# BaseStationCPU.net
KiCad netlist of a schematic drawn in Altium Designer
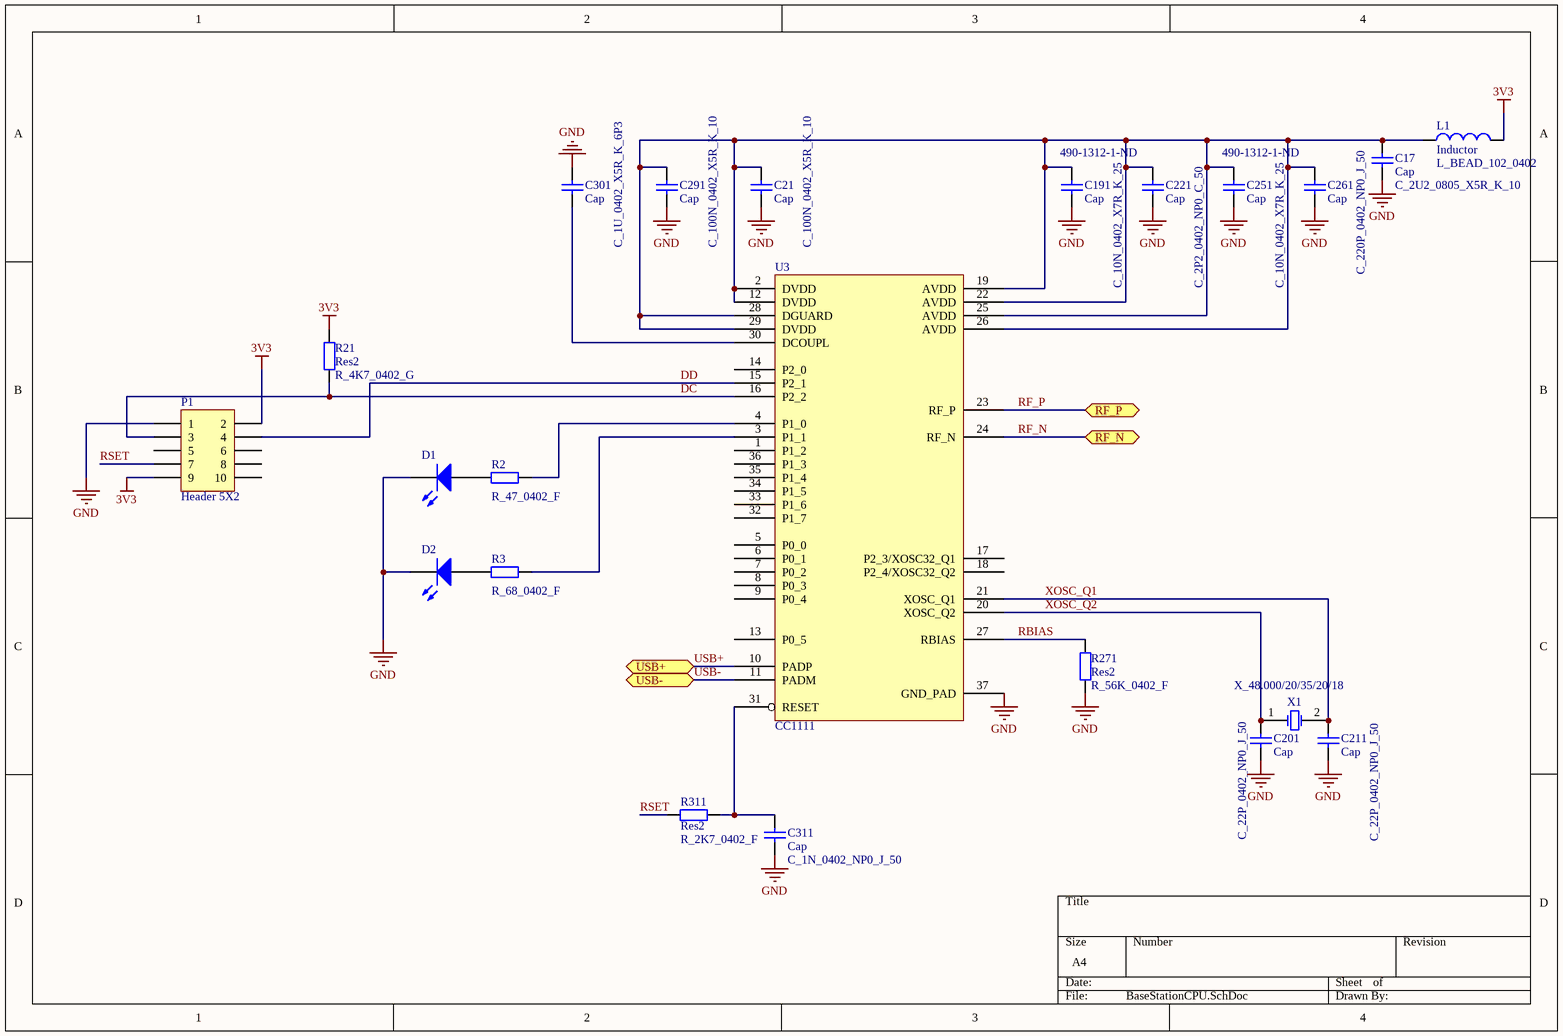
[diagram p0: BaseStationCPU.SchDoc]

(export (version "E")
  (design (tool "Eeschema 10.0.6"))
  (components
    (comp (ref "C17")
      (value "Cap")
      (footprint "C_0805")
      (description "Capacitor")
      (fields (field (name "ALTIUM_VALUE") "C_2U2_0805_X5R_K_10") (field (name "PUBLISHER") "Altium Limited"))
      (libsource (lib "Miscellaneous Devices") (part "Cap"))
    )
    (comp (ref "C21")
      (value "Cap")
      (footprint "C_0402")
      (description "Capacitor")
      (fields
        (field (name "ALTIUM_VALUE") "C_100N_0402_X5R_K_10")
        (field (name "PUBLISHER") "Altium Limited")
      )
      (libsource (lib "Miscellaneous Devices") (part "Cap"))
    )
    (comp (ref "C191")
      (value "Cap")
      (footprint "C_0402")
      (description "Capacitor")
      (fields
        (field (name "ALTIUM_VALUE") "C_10N_0402_X7R_K_25")
        (field (name "SUPPLIER PART NUMBER 1") "490-1312-1-ND")
        (field (name "PUBLISHER") "Altium Limited")
      )
      (libsource (lib "Miscellaneous Devices") (part "Cap"))
    )
    (comp (ref "C201")
      (value "Cap")
      (footprint "C_0402")
      (description "Capacitor")
      (fields (field (name "ALTIUM_VALUE") "C_22P_0402_NP0_J_50") (field (name "PUBLISHER") "Altium Limited"))
      (libsource (lib "Miscellaneous Devices") (part "Cap"))
    )
    (comp (ref "C211")
      (value "Cap")
      (footprint "C_0402")
      (description "Capacitor")
      (fields (field (name "ALTIUM_VALUE") "C_22P_0402_NP0_J_50") (field (name "PUBLISHER") "Altium Limited"))
      (libsource (lib "Miscellaneous Devices") (part "Cap"))
    )
    (comp (ref "C221")
      (value "Cap")
      (footprint "C_0402")
      (description "Capacitor")
      (fields (field (name "ALTIUM_VALUE") "C_2P2_0402_NP0_C_50") (field (name "PUBLISHER") "Altium Limited"))
      (libsource (lib "Miscellaneous Devices") (part "Cap"))
    )
    (comp (ref "C251")
      (value "Cap")
      (footprint "C_0402")
      (description "Capacitor")
      (fields
        (field (name "ALTIUM_VALUE") "C_10N_0402_X7R_K_25")
        (field (name "SUPPLIER PART NUMBER 1") "490-1312-1-ND")
        (field (name "PUBLISHER") "Altium Limited")
      )
      (libsource (lib "Miscellaneous Devices") (part "Cap"))
    )
    (comp (ref "C261")
      (value "Cap")
      (footprint "C_0402")
      (description "Capacitor")
      (fields
        (field (name "ALTIUM_VALUE") "C_220P_0402_NP0_J_50")
        (field (name "PUBLISHER") "Altium Limited")
      )
      (libsource (lib "Miscellaneous Devices") (part "Cap"))
    )
    (comp (ref "C291")
      (value "Cap")
      (footprint "C_0402")
      (description "Capacitor")
      (fields
        (field (name "ALTIUM_VALUE") "C_100N_0402_X5R_K_10")
        (field (name "PUBLISHER") "Altium Limited")
      )
      (libsource (lib "Miscellaneous Devices") (part "Cap"))
    )
    (comp (ref "C301")
      (value "Cap")
      (footprint "C_0402")
      (description "Capacitor")
      (fields (field (name "ALTIUM_VALUE") "C_1U_0402_X5R_K_6P3") (field (name "PUBLISHER") "Altium Limited"))
      (libsource (lib "Miscellaneous Devices") (part "Cap"))
    )
    (comp (ref "C311")
      (value "Cap")
      (footprint "C_0402")
      (description "Capacitor")
      (fields (field (name "ALTIUM_VALUE") "C_1N_0402_NP0_J_50") (field (name "PUBLISHER") "Altium Limited"))
      (libsource (lib "Miscellaneous Devices") (part "Cap"))
    )
    (comp (ref "D1")
      (value "LED_EL19-21SYGC")
      (footprint "R_0603")
      (description "LED ALINGAP YW/GN CLEAR 0603 SMD")
      (fields (field (name "PUBLISHER") "Altium Limited"))
      (libsource (lib "Miscellaneous Devices") (part "LED2"))
    )
    (comp (ref "D2")
      (value "LED_EL19-21SYGC")
      (footprint "R_0603")
      (description "LED 660NM RED WTR CLR 0603 SMD")
      (fields (field (name "PUBLISHER") "Altium Limited"))
      (libsource (lib "Miscellaneous Devices") (part "LED2"))
    )
    (comp (ref "L1")
      (value "Inductor")
      (footprint "R_0402")
      (fields (field (name "ALTIUM_VALUE") "L_BEAD_102_0402") (field (name "PUBLISHER") "Altium Limited"))
      (libsource (lib "Miscellaneous Devices") (part "Inductor"))
    )
    (comp (ref "P1")
      (value "Header 5X2")
      (footprint "SMD HEADER")
      (description "Header, 5-Pin, Dual row")
      (fields (field (name "PUBLISHER") "Altium Limited"))
      (libsource (lib "Miscellaneous Connectors") (part "Header 5X2"))
    )
    (comp (ref "R2")
      (value "R_47_0402_F")
      (footprint "R_0402")
      (description "Resistor")
      (fields (field (name "Comment") "Res2") (field (name "PUBLISHER") "Altium Limited"))
      (libsource (lib "Miscellaneous Devices") (part "Res2"))
    )
    (comp (ref "R3")
      (value "R_68_0402_F")
      (footprint "R_0402")
      (description "Resistor")
      (fields (field (name "Comment") "Res2") (field (name "PUBLISHER") "Altium Limited"))
      (libsource (lib "Miscellaneous Devices") (part "Res2"))
    )
    (comp (ref "R21")
      (value "Res2")
      (footprint "R_0402")
      (description "Resistor")
      (fields (field (name "ALTIUM_VALUE") "R_4K7_0402_G") (field (name "PUBLISHER") "Altium Limited"))
      (libsource (lib "") (part "Res2_1"))
    )
    (comp (ref "R271")
      (value "Res2")
      (footprint "R_0402")
      (description "Resistor")
      (fields (field (name "ALTIUM_VALUE") "R_56K_0402_F") (field (name "PUBLISHER") "Altium Limited"))
      (libsource (lib "") (part "Res2_1"))
    )
    (comp (ref "R311")
      (value "Res2")
      (footprint "R_0402")
      (description "Resistor")
      (fields (field (name "ALTIUM_VALUE") "R_2K7_0402_F") (field (name "PUBLISHER") "Altium Limited"))
      (libsource (lib "Miscellaneous Devices") (part "Res2"))
    )
    (comp (ref "U3")
      (value "CC1111")
      (footprint "TI_QFP36")
      (description "RF Microcontrollers (MCU) True System-on-Chip")
      (fields
        (field (name "MANUFACTURER") "Texas Instruments")
        (field (name "MANUFACTURER PART NUMBER") "CC1110F32RSPR")
      )
      (libsource (lib "BrewBit") (part "CC1111"))
    )
    (comp (ref "X1")
      (value "X_48.000/20/35/20/18")
      (footprint "CX3225GB48000D0HEQZ1")
      (description "Crystal Oscillator")
      (fields (field (name "PUBLISHER") "Altium Limited"))
      (libsource (lib "Miscellaneous Devices") (part "XTAL"))
    )
  )
  (nets
    (net (code "1") (name "/DC") (class "Default")
      (node (ref "P1") (pin "3") (pinfunction "3_3") (pintype "passive"))
      (node (ref "R21") (pin "1") (pinfunction "1_1") (pintype "passive"))
      (node (ref "U3") (pin "16") (pinfunction "P2_2_16") (pintype "passive"))
    )
    (net (code "2") (name "/DD") (class "Default")
      (node (ref "P1") (pin "4") (pinfunction "4_4") (pintype "passive"))
      (node (ref "U3") (pin "15") (pinfunction "P2_1_15") (pintype "passive"))
    )
    (net (code "3") (name "/RBIAS") (class "Default")
      (node (ref "R271") (pin "2") (pinfunction "2_2") (pintype "passive"))
      (node (ref "U3") (pin "27") (pinfunction "RBIAS_27") (pintype "passive"))
    )
    (net (code "4") (name "/RF_N") (class "Default")
      (node (ref "U3") (pin "24") (pinfunction "RF_N_24") (pintype "passive"))
    )
    (net (code "5") (name "/RF_P") (class "Default")
      (node (ref "U3") (pin "23") (pinfunction "RF_P_23") (pintype "passive"))
    )
    (net (code "6") (name "/RSET") (class "Default")
      (node (ref "P1") (pin "7") (pinfunction "7_7") (pintype "passive"))
      (node (ref "R311") (pin "1") (pinfunction "1_1") (pintype "passive"))
    )
    (net (code "7") (name "/USB+") (class "Default")
      (node (ref "U3") (pin "10") (pinfunction "PADP_10") (pintype "passive"))
    )
    (net (code "8") (name "/USB-") (class "Default")
      (node (ref "U3") (pin "11") (pinfunction "PADM_11") (pintype "passive"))
    )
    (net (code "9") (name "/XOSC_Q1") (class "Default")
      (node (ref "C211") (pin "2") (pinfunction "2_2") (pintype "passive"))
      (node (ref "U3") (pin "21") (pinfunction "XOSC_Q1_21") (pintype "passive"))
      (node (ref "X1") (pin "2") (pinfunction "OSC2_2") (pintype "passive"))
    )
    (net (code "10") (name "/XOSC_Q2") (class "Default")
      (node (ref "C201") (pin "2") (pinfunction "2_2") (pintype "passive"))
      (node (ref "U3") (pin "20") (pinfunction "XOSC_Q2_20") (pintype "passive"))
      (node (ref "X1") (pin "1") (pinfunction "OSC1_1") (pintype "passive"))
    )
    (net (code "11") (name "3V3") (class "Default")
      (node (ref "L1") (pin "2") (pinfunction "2_2") (pintype "passive"))
      (node (ref "P1") (pin "2") (pinfunction "2_2") (pintype "passive"))
      (node (ref "P1") (pin "9") (pinfunction "9_9") (pintype "passive"))
      (node (ref "R21") (pin "2") (pinfunction "2_2") (pintype "passive"))
    )
    (net (code "12") (name "GND") (class "Default")
      (node (ref "C17") (pin "1") (pinfunction "1_1") (pintype "passive"))
      (node (ref "C191") (pin "1") (pinfunction "1_1") (pintype "passive"))
      (node (ref "C201") (pin "1") (pinfunction "1_1") (pintype "passive"))
      (node (ref "C21") (pin "1") (pinfunction "1_1") (pintype "passive"))
      (node (ref "C211") (pin "1") (pinfunction "1_1") (pintype "passive"))
      (node (ref "C221") (pin "1") (pinfunction "1_1") (pintype "passive"))
      (node (ref "C251") (pin "1") (pinfunction "1_1") (pintype "passive"))
      (node (ref "C261") (pin "1") (pinfunction "1_1") (pintype "passive"))
      (node (ref "C291") (pin "1") (pinfunction "1_1") (pintype "passive"))
      (node (ref "C301") (pin "2") (pinfunction "2_2") (pintype "passive"))
      (node (ref "C311") (pin "1") (pinfunction "1_1") (pintype "passive"))
      (node (ref "D1") (pin "2") (pinfunction "K_2") (pintype "passive"))
      (node (ref "D2") (pin "2") (pinfunction "K_2") (pintype "passive"))
      (node (ref "P1") (pin "1") (pinfunction "1_1") (pintype "passive"))
      (node (ref "R271") (pin "1") (pinfunction "1_1") (pintype "passive"))
      (node (ref "U3") (pin "37") (pinfunction "GND_PAD_37") (pintype "passive"))
    )
    (net (code "13") (name "Net-(D1-A)") (class "Default")
      (node (ref "D1") (pin "1") (pinfunction "A_1") (pintype "passive"))
      (node (ref "R2") (pin "1") (pinfunction "1_1") (pintype "passive"))
    )
    (net (code "14") (name "Net-(D2-A)") (class "Default")
      (node (ref "D2") (pin "1") (pinfunction "A_1") (pintype "passive"))
      (node (ref "R3") (pin "1") (pinfunction "1_1") (pintype "passive"))
    )
    (net (code "15") (name "Net-(U3-DCOUPL)") (class "Default")
      (node (ref "C301") (pin "1") (pinfunction "1_1") (pintype "passive"))
      (node (ref "U3") (pin "30") (pinfunction "DCOUPL_30") (pintype "passive"))
    )
    (net (code "16") (name "Net-(U3-DGUARD)") (class "Default")
      (node (ref "C17") (pin "2") (pinfunction "2_2") (pintype "passive"))
      (node (ref "C191") (pin "2") (pinfunction "2_2") (pintype "passive"))
      (node (ref "C21") (pin "2") (pinfunction "2_2") (pintype "passive"))
      (node (ref "C221") (pin "2") (pinfunction "2_2") (pintype "passive"))
      (node (ref "C251") (pin "2") (pinfunction "2_2") (pintype "passive"))
      (node (ref "C261") (pin "2") (pinfunction "2_2") (pintype "passive"))
      (node (ref "C291") (pin "2") (pinfunction "2_2") (pintype "passive"))
      (node (ref "L1") (pin "1") (pinfunction "1_1") (pintype "passive"))
      (node (ref "U3") (pin "12") (pinfunction "DVDD_12") (pintype "passive"))
      (node (ref "U3") (pin "19") (pinfunction "AVDD_19") (pintype "passive"))
      (node (ref "U3") (pin "2") (pinfunction "DVDD_2") (pintype "passive"))
      (node (ref "U3") (pin "22") (pinfunction "AVDD_22") (pintype "passive"))
      (node (ref "U3") (pin "25") (pinfunction "AVDD_25") (pintype "passive"))
      (node (ref "U3") (pin "26") (pinfunction "AVDD_26") (pintype "passive"))
      (node (ref "U3") (pin "28") (pinfunction "DGUARD_28") (pintype "passive"))
      (node (ref "U3") (pin "29") (pinfunction "DVDD_29") (pintype "passive"))
    )
    (net (code "17") (name "Net-(U3-P1_0)") (class "Default")
      (node (ref "R2") (pin "2") (pinfunction "2_2") (pintype "passive"))
      (node (ref "U3") (pin "4") (pinfunction "P1_0_4") (pintype "passive"))
    )
    (net (code "18") (name "Net-(U3-P1_1)") (class "Default")
      (node (ref "R3") (pin "2") (pinfunction "2_2") (pintype "passive"))
      (node (ref "U3") (pin "3") (pinfunction "P1_1_3") (pintype "passive"))
    )
    (net (code "19") (name "Net-(U3-RESET)") (class "Default")
      (node (ref "C311") (pin "2") (pinfunction "2_2") (pintype "passive"))
      (node (ref "R311") (pin "2") (pinfunction "2_2") (pintype "passive"))
      (node (ref "U3") (pin "31") (pinfunction "RESET_31") (pintype "passive"))
    )
    (net (code "20") (name "unconnected-(P1-Pad5)") (class "Default")
      (node (ref "P1") (pin "5") (pinfunction "5_5") (pintype "passive"))
    )
    (net (code "21") (name "unconnected-(P1-Pad6)") (class "Default")
      (node (ref "P1") (pin "6") (pinfunction "6_6") (pintype "passive"))
    )
    (net (code "22") (name "unconnected-(P1-Pad8)") (class "Default")
      (node (ref "P1") (pin "8") (pinfunction "8_8") (pintype "passive"))
    )
    (net (code "23") (name "unconnected-(P1-Pad10)") (class "Default")
      (node (ref "P1") (pin "10") (pinfunction "10_10") (pintype "passive"))
    )
    (net (code "24") (name "unconnected-(U3-P0_0-Pad5)") (class "Default")
      (node (ref "U3") (pin "5") (pinfunction "P0_0_5") (pintype "passive"))
    )
    (net (code "25") (name "unconnected-(U3-P0_1-Pad6)") (class "Default")
      (node (ref "U3") (pin "6") (pinfunction "P0_1_6") (pintype "passive"))
    )
    (net (code "26") (name "unconnected-(U3-P0_2-Pad7)") (class "Default")
      (node (ref "U3") (pin "7") (pinfunction "P0_2_7") (pintype "passive"))
    )
    (net (code "27") (name "unconnected-(U3-P0_3-Pad8)") (class "Default")
      (node (ref "U3") (pin "8") (pinfunction "P0_3_8") (pintype "passive"))
    )
    (net (code "28") (name "unconnected-(U3-P0_4-Pad9)") (class "Default")
      (node (ref "U3") (pin "9") (pinfunction "P0_4_9") (pintype "passive"))
    )
    (net (code "29") (name "unconnected-(U3-P0_5-Pad13)") (class "Default")
      (node (ref "U3") (pin "13") (pinfunction "P0_5_13") (pintype "passive"))
    )
    (net (code "30") (name "unconnected-(U3-P1_2-Pad1)") (class "Default")
      (node (ref "U3") (pin "1") (pinfunction "P1_2_1") (pintype "passive"))
    )
    (net (code "31") (name "unconnected-(U3-P1_3-Pad36)") (class "Default")
      (node (ref "U3") (pin "36") (pinfunction "P1_3_36") (pintype "passive"))
    )
    (net (code "32") (name "unconnected-(U3-P1_4-Pad35)") (class "Default")
      (node (ref "U3") (pin "35") (pinfunction "P1_4_35") (pintype "passive"))
    )
    (net (code "33") (name "unconnected-(U3-P1_5-Pad34)") (class "Default")
      (node (ref "U3") (pin "34") (pinfunction "P1_5_34") (pintype "passive"))
    )
    (net (code "34") (name "unconnected-(U3-P1_6-Pad33)") (class "Default")
      (node (ref "U3") (pin "33") (pinfunction "P1_6_33") (pintype "passive"))
    )
    (net (code "35") (name "unconnected-(U3-P1_7-Pad32)") (class "Default")
      (node (ref "U3") (pin "32") (pinfunction "P1_7_32") (pintype "passive"))
    )
    (net (code "36") (name "unconnected-(U3-P2_0-Pad14)") (class "Default")
      (node (ref "U3") (pin "14") (pinfunction "P2_0_14") (pintype "passive"))
    )
    (net (code "37") (name "unconnected-(U3-P2_3{slash}XOSC32_Q1-Pad17)") (class "Default")
      (node (ref "U3") (pin "17") (pinfunction "P2_3/XOSC32_Q1_17") (pintype "passive"))
    )
    (net (code "38") (name "unconnected-(U3-P2_4{slash}XOSC32_Q2-Pad18)") (class "Default")
      (node (ref "U3") (pin "18") (pinfunction "P2_4/XOSC32_Q2_18") (pintype "passive"))
    )
  )
)
